# SCH_My-first-PCB-hacker-card_2024-07-06.net
KiCad netlist of a schematic drawn in EasyEDA
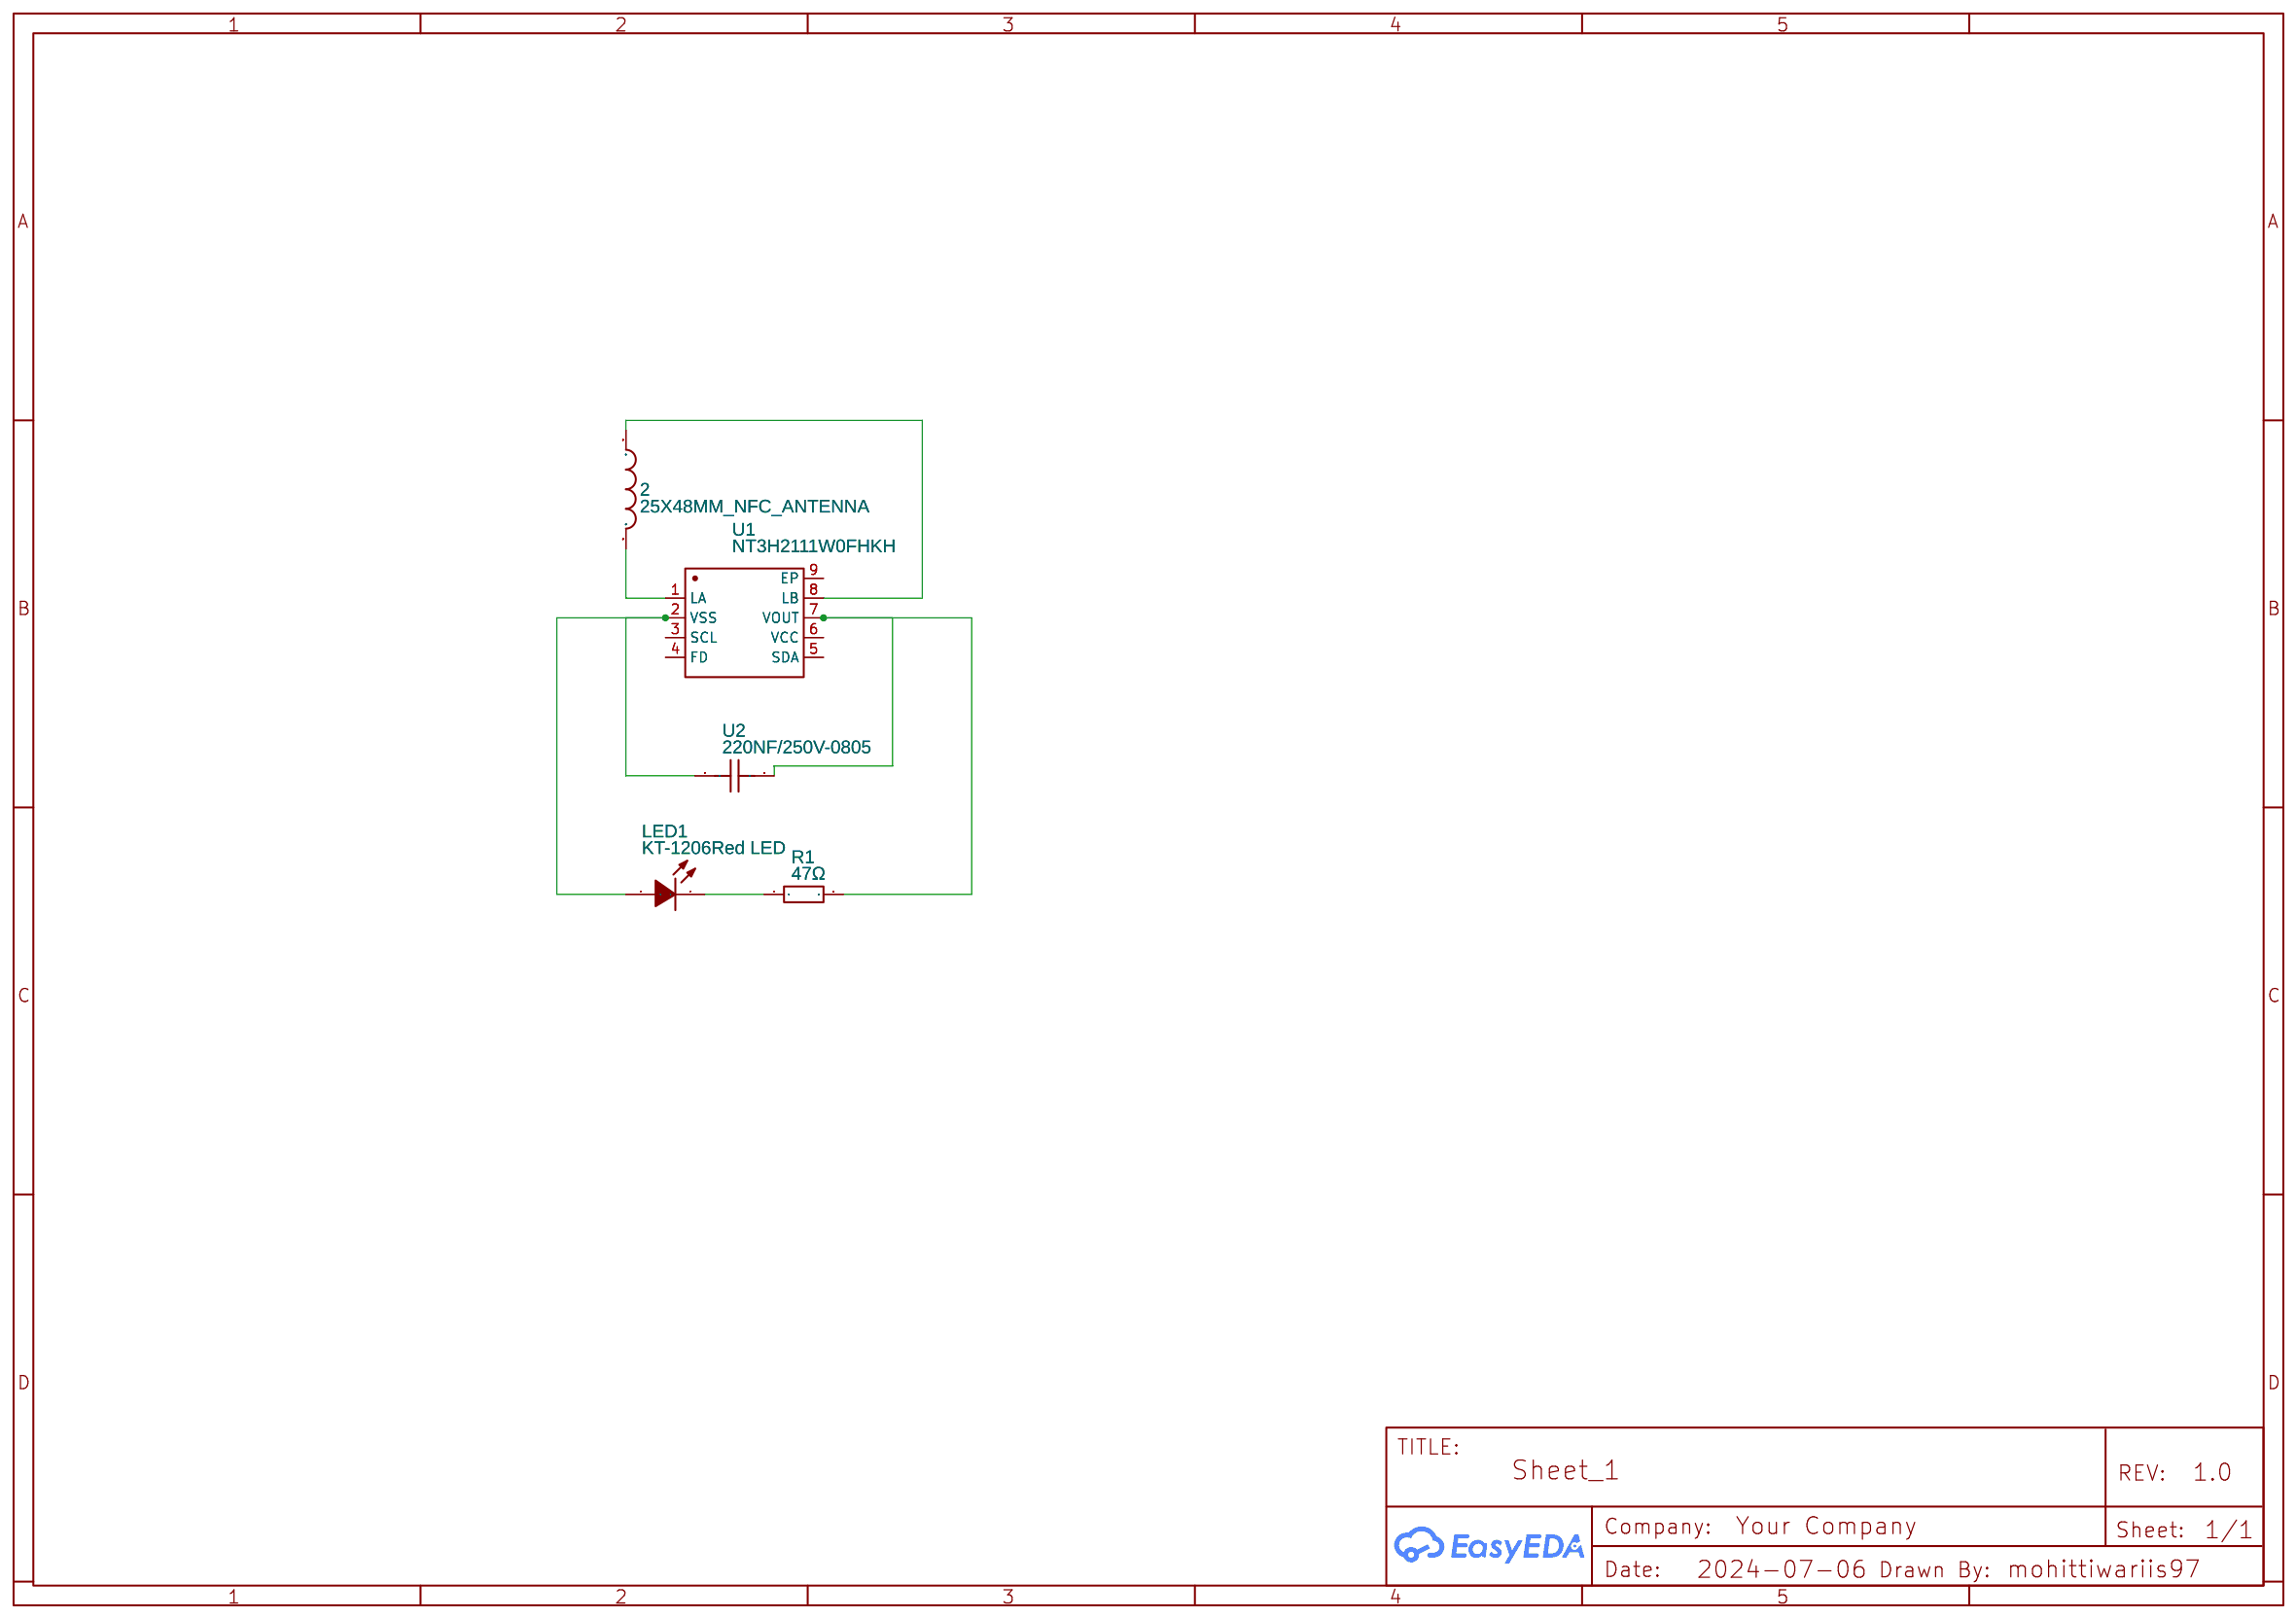
[diagram p0: schematic sheet]

(export (version "E")
  (design (tool "Eeschema 10.0.6"))
  (components
    (comp (ref "2") (value "25X48MM_NFC_ANTENNA") (libsource (lib "") (part "25X48MM_NFC_ANTENNA")))
    (comp (ref "LED1")
      (value "KT-1206Red LED")
      (fields (field (name "Manufacturer Part") "KT-1206R") (field (name "Manufacturer") "KENTO"))
      (libsource (lib "") (part "KT-1206Red LED"))
    )
    (comp (ref "R1")
      (value "47Ω")
      (fields (field (name "Manufacturer Part") "KNP2W-47Ω±5% MK型") (field (name "Manufacturer") "CCO(千志电子)"))
      (libsource (lib "") (part "47Ω(470) ±5%"))
    )
    (comp (ref "U1")
      (value "NT3H2111W0FHKH")
      (fields (field (name "Manufacturer") "NXP(恩智浦)"))
      (libsource (lib "") (part "NT3H2111W0FHKH"))
    )
    (comp (ref "U2")
      (value "220NF/250V-0805")
      (fields (field (name "Manufacturer Part") "220nF/250V-0805"))
      (libsource (lib "") (part "220NF/250V-0805"))
    )
  )
  (nets
    (net (code "1") (name "Net-(LED1-A)") (class "Default")
      (node (ref "LED1") (pin "1") (pinfunction "A_1") (pintype "unspecified"))
      (node (ref "U1") (pin "2") (pinfunction "VSS_2") (pintype "unspecified"))
      (node (ref "U2") (pin "1") (pinfunction "1_1") (pintype "unspecified"))
    )
    (net (code "2") (name "Net-(LED1-K)") (class "Default")
      (node (ref "LED1") (pin "2") (pinfunction "K_2") (pintype "unspecified"))
      (node (ref "R1") (pin "1") (pinfunction "1_1") (pintype "unspecified"))
    )
    (net (code "3") (name "Net-(U1-LA)") (class "Default")
      (node (ref "2") (pin "P$2") (pinfunction "P$2_P$2") (pintype "bidirectional"))
      (node (ref "U1") (pin "1") (pinfunction "LA_1") (pintype "unspecified"))
    )
    (net (code "4") (name "Net-(U1-LB)") (class "Default")
      (node (ref "2") (pin "P$1") (pinfunction "P$1_P$1") (pintype "bidirectional"))
      (node (ref "U1") (pin "8") (pinfunction "LB_8") (pintype "unspecified"))
    )
    (net (code "5") (name "Net-(U1-VOUT)") (class "Default")
      (node (ref "R1") (pin "2") (pinfunction "2_2") (pintype "unspecified"))
      (node (ref "U1") (pin "7") (pinfunction "VOUT_7") (pintype "unspecified"))
      (node (ref "U2") (pin "2") (pinfunction "2_2") (pintype "unspecified"))
    )
    (net (code "6") (name "unconnected-(U1-EP-Pad9)") (class "Default")
      (node (ref "U1") (pin "9") (pinfunction "EP_9") (pintype "unspecified"))
    )
    (net (code "7") (name "unconnected-(U1-FD-Pad4)") (class "Default")
      (node (ref "U1") (pin "4") (pinfunction "FD_4") (pintype "unspecified"))
    )
    (net (code "8") (name "unconnected-(U1-SCL-Pad3)") (class "Default")
      (node (ref "U1") (pin "3") (pinfunction "SCL_3") (pintype "unspecified"))
    )
    (net (code "9") (name "unconnected-(U1-SDA-Pad5)") (class "Default")
      (node (ref "U1") (pin "5") (pinfunction "SDA_5") (pintype "unspecified"))
    )
    (net (code "10") (name "unconnected-(U1-VCC-Pad6)") (class "Default")
      (node (ref "U1") (pin "6") (pinfunction "VCC_6") (pintype "unspecified"))
    )
  )
)
